# 006P-5VSupply.net
KiCad netlist of a schematic drawn in EAGLE
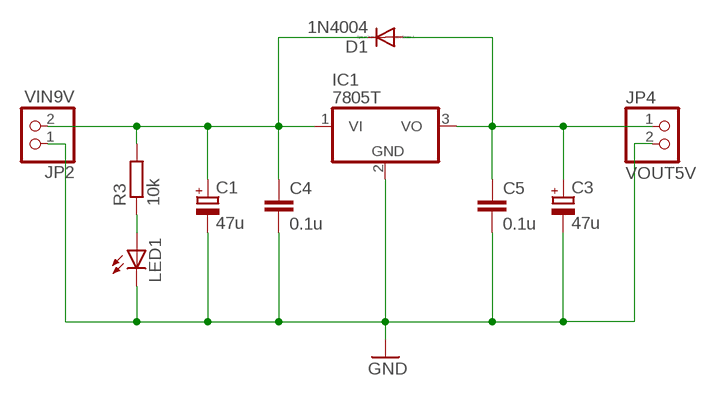
[diagram p0: schematic, sheet 1]

(export (version "E")
  (design (tool "Eeschema 10.0.6"))
  (components
    (comp (ref "C1")
      (value "47u")
      (footprint "eagle-import:E2-4")
      (libsource (lib "eagle-import") (part "CPOL-EUE2-4"))
    )
    (comp (ref "C3")
      (value "47u")
      (footprint "eagle-import:E2-4")
      (libsource (lib "eagle-import") (part "CPOL-EUE2-4"))
    )
    (comp (ref "C4")
      (value "0.1u")
      (footprint "eagle-import:C025-024X044")
      (libsource (lib "eagle-import") (part "C-EU025-024X044"))
    )
    (comp (ref "C5")
      (value "0.1u")
      (footprint "eagle-import:C025-024X044")
      (libsource (lib "eagle-import") (part "C-EU025-024X044"))
    )
    (comp (ref "D1")
      (value "1N4004")
      (footprint "eagle-import:DO41-10")
      (libsource (lib "eagle-import") (part "1N4004"))
    )
    (comp (ref "IC1")
      (value "7805T")
      (footprint "eagle-import:TO220H")
      (libsource (lib "eagle-import") (part "78T05"))
    )
    (comp (ref "JP2")
      (value "VIN9V")
      (footprint "eagle-import:1X02")
      (libsource (lib "eagle-import") (part "PINHD-1X2"))
    )
    (comp (ref "JP4")
      (value "VOUT5V")
      (footprint "eagle-import:1X02")
      (libsource (lib "eagle-import") (part "PINHD-1X2"))
    )
    (comp (ref "LED1")
      (value "LED3MM")
      (footprint "eagle-import:LED3MM")
      (libsource (lib "eagle-import") (part "LED3MM"))
    )
    (comp (ref "R3")
      (value "10k")
      (footprint "eagle-import:0207_7")
      (libsource (lib "eagle-import") (part "R-EU_0207/7"))
    )
  )
  (nets
    (net (code "1") (name "GND") (class "Default")
      (node (ref "C1") (pin "-") (pinfunction "-_-") (pintype "passive"))
      (node (ref "C3") (pin "-") (pinfunction "-_-") (pintype "passive"))
      (node (ref "C4") (pin "2") (pinfunction "2_2") (pintype "passive"))
      (node (ref "C5") (pin "2") (pinfunction "2_2") (pintype "passive"))
      (node (ref "IC1") (pin "2") (pinfunction "GND_2") (pintype "passive"))
      (node (ref "JP2") (pin "1") (pinfunction "1_1") (pintype "passive"))
      (node (ref "JP4") (pin "2") (pinfunction "2_2") (pintype "passive"))
      (node (ref "LED1") (pin "K") (pinfunction "C_K") (pintype "passive"))
    )
    (net (code "2") (name "Net-(IC1-VI)") (class "Default")
      (node (ref "C1") (pin "+") (pinfunction "+_+") (pintype "passive"))
      (node (ref "C4") (pin "1") (pinfunction "1_1") (pintype "passive"))
      (node (ref "D1") (pin "C") (pinfunction "C_C") (pintype "passive"))
      (node (ref "IC1") (pin "1") (pinfunction "VI_1") (pintype "input"))
      (node (ref "JP2") (pin "2") (pinfunction "2_2") (pintype "passive"))
      (node (ref "R3") (pin "2") (pinfunction "2_2") (pintype "passive"))
    )
    (net (code "3") (name "Net-(IC1-VO)") (class "Default")
      (node (ref "C3") (pin "+") (pinfunction "+_+") (pintype "passive"))
      (node (ref "C5") (pin "1") (pinfunction "1_1") (pintype "passive"))
      (node (ref "D1") (pin "A") (pinfunction "A_A") (pintype "passive"))
      (node (ref "IC1") (pin "3") (pinfunction "VO_3") (pintype "passive"))
      (node (ref "JP4") (pin "1") (pinfunction "1_1") (pintype "passive"))
    )
    (net (code "4") (name "Net-(LED1-PadA)") (class "Default")
      (node (ref "LED1") (pin "A") (pinfunction "A_A") (pintype "passive"))
      (node (ref "R3") (pin "1") (pinfunction "1_1") (pintype "passive"))
    )
  )
)
